# fish-2_0.net
KiCad netlist of a schematic drawn in EAGLE
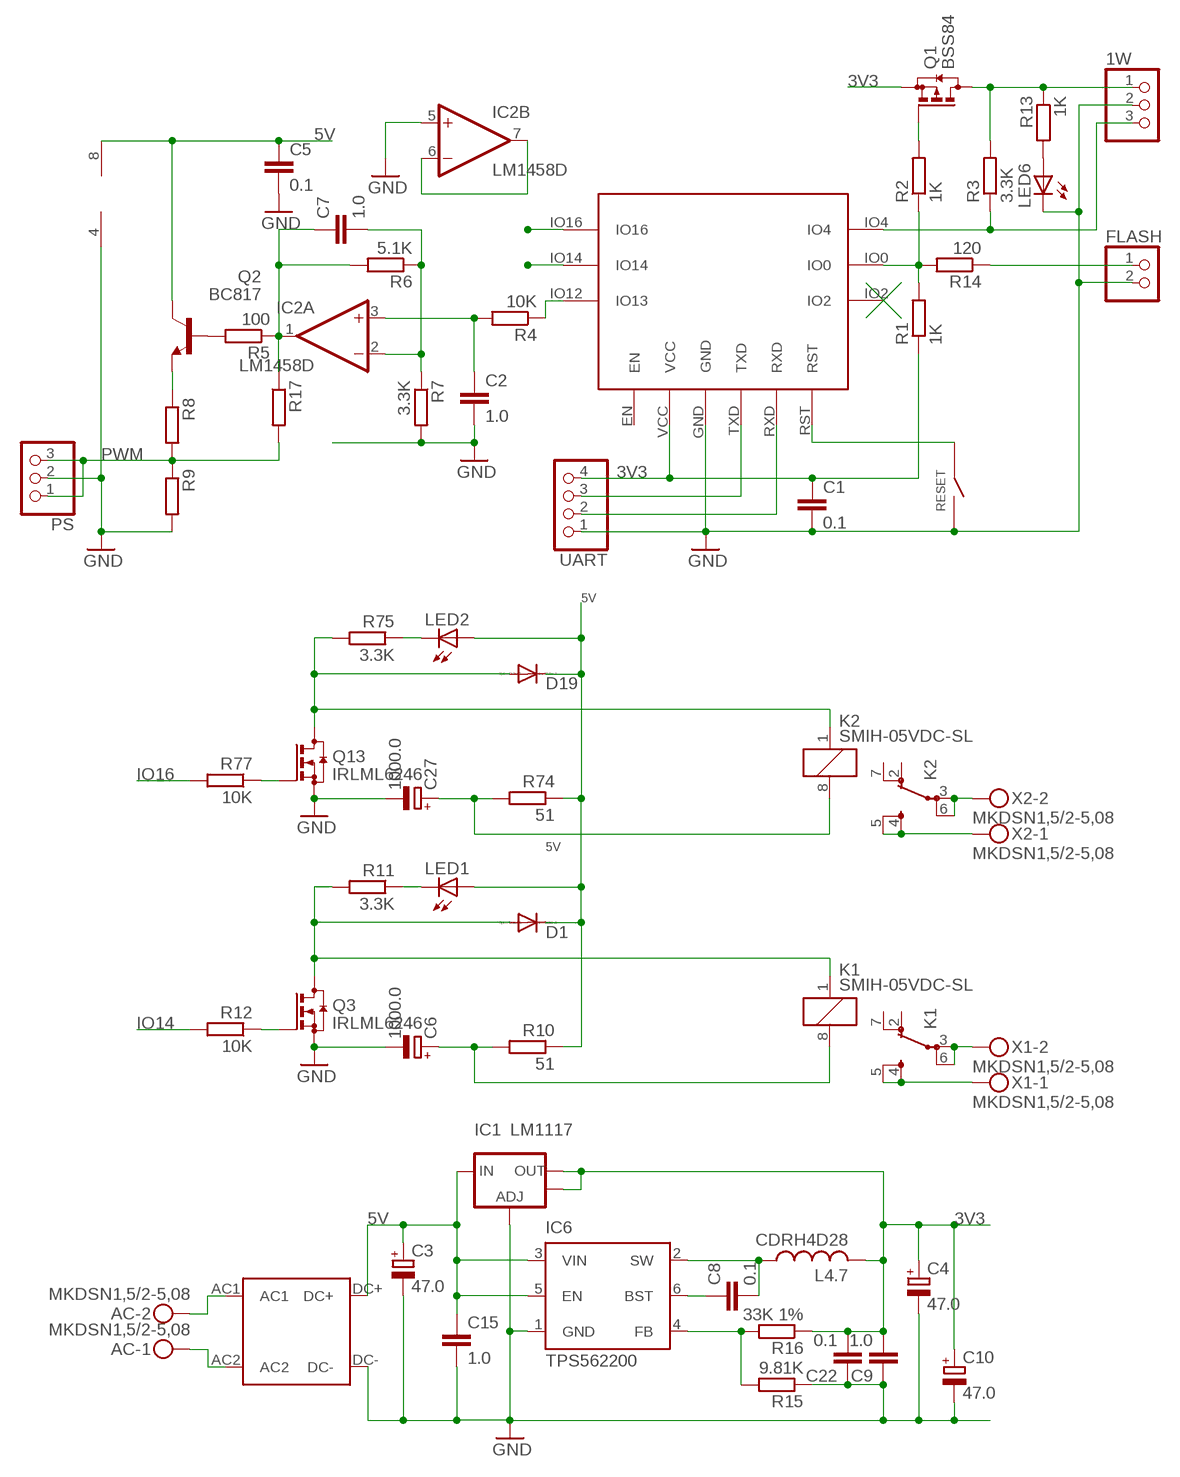
[diagram p0: schematic, sheet 1]

(export (version "E")
  (design (tool "Eeschema 10.0.6"))
  (components
    (comp (ref "1W")
      (value "PINHD-1X3/90")
      (footprint "eagle-import:1X03_90")
      (libsource (lib "eagle-import") (part "PINHD-1X3/90"))
    )
    (comp (ref "AC")
      (value "MKDSN1,5/2-5,08")
      (footprint "eagle-import:MKDSN1,5_2-5,08")
      (libsource (lib "eagle-import") (part "MKDSN1,5/2-5,08"))
    )
    (comp (ref "C1")
      (value "0.1")
      (footprint "eagle-import:C0805")
      (libsource (lib "eagle-import") (part "C-EUC0805"))
    )
    (comp (ref "C2")
      (value "1.0")
      (footprint "eagle-import:C0805")
      (libsource (lib "eagle-import") (part "C-EUC0805"))
    )
    (comp (ref "C3")
      (value "47.0")
      (footprint "eagle-import:SMC_D")
      (libsource (lib "eagle-import") (part "CPOL-EUSMCD"))
    )
    (comp (ref "C4")
      (value "47.0")
      (footprint "eagle-import:SMC_B")
      (libsource (lib "eagle-import") (part "CPOL-EUSMCB"))
    )
    (comp (ref "C5")
      (value "0.1")
      (footprint "eagle-import:C0805")
      (libsource (lib "eagle-import") (part "C-EUC0805"))
    )
    (comp (ref "C6")
      (value "1000.0")
      (footprint "eagle-import:E3,5-8")
      (libsource (lib "eagle-import") (part "CPOL-EUE3.5-8"))
    )
    (comp (ref "C7")
      (value "1.0")
      (footprint "eagle-import:C0805")
      (libsource (lib "eagle-import") (part "C-EUC0805"))
    )
    (comp (ref "C8")
      (value "0.1")
      (footprint "eagle-import:C0805")
      (libsource (lib "eagle-import") (part "C-EUC0805"))
    )
    (comp (ref "C9")
      (value "1.0")
      (footprint "eagle-import:C0805")
      (libsource (lib "eagle-import") (part "C-EUC0805"))
    )
    (comp (ref "C10")
      (value "47.0")
      (footprint "eagle-import:SMC_D")
      (libsource (lib "eagle-import") (part "CPOL-EUSMCD"))
    )
    (comp (ref "C15")
      (value "1.0")
      (footprint "eagle-import:C0805")
      (libsource (lib "eagle-import") (part "C-EUC0805"))
    )
    (comp (ref "C22")
      (value "0.1")
      (footprint "eagle-import:C0805")
      (libsource (lib "eagle-import") (part "C-EUC0805"))
    )
    (comp (ref "C27")
      (value "1000.0")
      (footprint "eagle-import:E3,5-8")
      (libsource (lib "eagle-import") (part "CPOL-EUE3.5-8"))
    )
    (comp (ref "D1")
      (value "DIODE-SOD123")
      (footprint "eagle-import:SOD123")
      (libsource (lib "eagle-import") (part "DIODE-SOD123"))
    )
    (comp (ref "D19")
      (value "DIODE-SOD123")
      (footprint "eagle-import:SOD123")
      (libsource (lib "eagle-import") (part "DIODE-SOD123"))
    )
    (comp (ref "ESP-M3")
      (value "ESP-M3")
      (footprint "eagle-import:ESP-M3")
      (libsource (lib "eagle-import") (part "ESP-M3"))
    )
    (comp (ref "FLASH")
      (value "PINHD-1X2/90")
      (footprint "eagle-import:1X02_90")
      (libsource (lib "eagle-import") (part "PINHD-1X2/90"))
    )
    (comp (ref "IC1")
      (value "LM1117")
      (footprint "eagle-import:SOT223")
      (libsource (lib "eagle-import") (part "V_REG_LM1117SOT223"))
    )
    (comp (ref "IC2")
      (value "LM1458D")
      (footprint "eagle-import:SO08")
      (libsource (lib "eagle-import") (part "1458DLM"))
    )
    (comp (ref "IC6")
      (value "TPS562200")
      (footprint "eagle-import:TSOT23-6_DDC")
      (libsource (lib "eagle-import") (part "TPS56X200"))
    )
    (comp (ref "K1")
      (value "SMIH-05VDC-SL")
      (footprint "eagle-import:FTR-K1C")
      (libsource (lib "eagle-import") (part "FTR-K1C"))
    )
    (comp (ref "K2")
      (value "SMIH-05VDC-SL")
      (footprint "eagle-import:FTR-K1C")
      (libsource (lib "eagle-import") (part "FTR-K1C"))
    )
    (comp (ref "L4.7")
      (value "CDRH4D28")
      (footprint "eagle-import:CDRH4D28")
      (libsource (lib "eagle-import") (part "CDRH4D28"))
    )
    (comp (ref "LED1")
      (value "LEDSMT1206")
      (footprint "eagle-import:1206")
      (libsource (lib "eagle-import") (part "LEDSMT1206"))
    )
    (comp (ref "LED2")
      (value "LEDSMT1206")
      (footprint "eagle-import:1206")
      (libsource (lib "eagle-import") (part "LEDSMT1206"))
    )
    (comp (ref "LED6")
      (value "LEDSMT1206")
      (footprint "eagle-import:1206")
      (libsource (lib "eagle-import") (part "LEDSMT1206"))
    )
    (comp (ref "PS")
      (value "PINHD-1X3/90")
      (footprint "eagle-import:1X03_90")
      (libsource (lib "eagle-import") (part "PINHD-1X3/90"))
    )
    (comp (ref "Q1")
      (value "BSS84")
      (footprint "eagle-import:SOT23")
      (libsource (lib "eagle-import") (part "BSS84"))
    )
    (comp (ref "Q2")
      (value "BC817")
      (footprint "eagle-import:SOT23-BEC")
      (libsource (lib "eagle-import") (part "BC817SMD-40"))
    )
    (comp (ref "Q3")
      (value "IRLML6246")
      (footprint "eagle-import:SOT23")
      (libsource (lib "eagle-import") (part "BSS123"))
    )
    (comp (ref "Q13")
      (value "IRLML6246")
      (footprint "eagle-import:SOT23")
      (libsource (lib "eagle-import") (part "BSS123"))
    )
    (comp (ref "R1")
      (value "1K")
      (footprint "eagle-import:R0603")
      (libsource (lib "eagle-import") (part "R-EU_R0603"))
    )
    (comp (ref "R2")
      (value "1K")
      (footprint "eagle-import:R0603")
      (libsource (lib "eagle-import") (part "R-EU_R0603"))
    )
    (comp (ref "R3")
      (value "3.3K")
      (footprint "eagle-import:R0603")
      (libsource (lib "eagle-import") (part "R-EU_R0603"))
    )
    (comp (ref "R4")
      (value "10K")
      (footprint "eagle-import:R0603")
      (libsource (lib "eagle-import") (part "R-EU_R0603"))
    )
    (comp (ref "R5")
      (value "100")
      (footprint "eagle-import:R0603")
      (libsource (lib "eagle-import") (part "R-EU_R0603"))
    )
    (comp (ref "R6")
      (value "5.1K")
      (footprint "eagle-import:R0603")
      (libsource (lib "eagle-import") (part "R-EU_R0603"))
    )
    (comp (ref "R7")
      (value "3.3K")
      (footprint "eagle-import:R0603")
      (libsource (lib "eagle-import") (part "R-EU_R0603"))
    )
    (comp (ref "R8")
      (value "R-EU_R0603")
      (footprint "eagle-import:R0603")
      (libsource (lib "eagle-import") (part "R-EU_R0603"))
    )
    (comp (ref "R9")
      (value "R-EU_R0603")
      (footprint "eagle-import:R0603")
      (libsource (lib "eagle-import") (part "R-EU_R0603"))
    )
    (comp (ref "R10")
      (value "51")
      (footprint "eagle-import:R1206")
      (libsource (lib "eagle-import") (part "R-EU_R1206"))
    )
    (comp (ref "R11")
      (value "3.3K")
      (footprint "eagle-import:R0603")
      (libsource (lib "eagle-import") (part "R-EU_R0603"))
    )
    (comp (ref "R12")
      (value "10K")
      (footprint "eagle-import:R0603")
      (libsource (lib "eagle-import") (part "R-EU_R0603"))
    )
    (comp (ref "R13")
      (value "1K")
      (footprint "eagle-import:R0603")
      (libsource (lib "eagle-import") (part "R-EU_R0603"))
    )
    (comp (ref "R14")
      (value "120")
      (footprint "eagle-import:R0603")
      (libsource (lib "eagle-import") (part "R-EU_R0603"))
    )
    (comp (ref "R15")
      (value "9.81K")
      (footprint "eagle-import:R0603")
      (libsource (lib "eagle-import") (part "R-EU_R0603"))
    )
    (comp (ref "R16")
      (value "33K 1%")
      (footprint "eagle-import:R0603")
      (libsource (lib "eagle-import") (part "R-EU_R0603"))
    )
    (comp (ref "R17")
      (value "R-EU_R0603")
      (footprint "eagle-import:R0603")
      (libsource (lib "eagle-import") (part "R-EU_R0603"))
    )
    (comp (ref "R74")
      (value "51")
      (footprint "eagle-import:R1206")
      (libsource (lib "eagle-import") (part "R-EU_R1206"))
    )
    (comp (ref "R75")
      (value "3.3K")
      (footprint "eagle-import:R0603")
      (libsource (lib "eagle-import") (part "R-EU_R0603"))
    )
    (comp (ref "R77")
      (value "10K")
      (footprint "eagle-import:R0603")
      (libsource (lib "eagle-import") (part "R-EU_R0603"))
    )
    (comp (ref "RESET")
      (value "TACT3X4")
      (footprint "eagle-import:TACT3X4")
      (libsource (lib "eagle-import") (part "TACT3X4"))
    )
    (comp (ref "U$1")
      (value "AC-DC/10W-12V")
      (footprint "eagle-import:AC-DC_10W")
      (libsource (lib "eagle-import") (part "AC-DC/10W-12V"))
    )
    (comp (ref "UART")
      (value "PINHD-1X4/90")
      (footprint "eagle-import:1X04_90")
      (libsource (lib "eagle-import") (part "PINHD-1X4/90"))
    )
    (comp (ref "X1")
      (value "MKDSN1,5/2-5,08")
      (footprint "eagle-import:MKDSN1,5_2-5,08")
      (libsource (lib "eagle-import") (part "MKDSN1,5/2-5,08"))
    )
    (comp (ref "X2")
      (value "MKDSN1,5/2-5,08")
      (footprint "eagle-import:MKDSN1,5_2-5,08")
      (libsource (lib "eagle-import") (part "MKDSN1,5/2-5,08"))
    )
  )
  (nets
    (net (code "1") (name "/3V3") (class "Default")
      (node (ref "C1") (pin "1") (pinfunction "1_1") (pintype "passive"))
      (node (ref "C10") (pin "+") (pinfunction "+_+") (pintype "passive"))
      (node (ref "C22") (pin "2") (pinfunction "2_2") (pintype "passive"))
      (node (ref "C4") (pin "+") (pinfunction "+_+") (pintype "passive"))
      (node (ref "C9") (pin "2") (pinfunction "2_2") (pintype "passive"))
      (node (ref "ESP-M3") (pin "VCC") (pinfunction "VCC_VCC") (pintype "bidirectional"))
      (node (ref "IC1") (pin "2") (pinfunction "OUT_2") (pintype "output"))
      (node (ref "IC1") (pin "4") (pinfunction "OUT_4") (pintype "output"))
      (node (ref "L4.7") (pin "P$2") (pinfunction "2_P$2") (pintype "passive"))
      (node (ref "Q1") (pin "2") (pinfunction "S_2") (pintype "passive"))
      (node (ref "R1") (pin "1") (pinfunction "1_1") (pintype "passive"))
      (node (ref "R16") (pin "1") (pinfunction "1_1") (pintype "passive"))
      (node (ref "UART") (pin "4") (pinfunction "4_4") (pintype "passive"))
    )
    (net (code "2") (name "/5V") (class "Default")
      (node (ref "C15") (pin "1") (pinfunction "1_1") (pintype "passive"))
      (node (ref "C3") (pin "+") (pinfunction "+_+") (pintype "passive"))
      (node (ref "C5") (pin "1") (pinfunction "1_1") (pintype "passive"))
      (node (ref "D1") (pin "C") (pinfunction "C_C") (pintype "passive"))
      (node (ref "D19") (pin "C") (pinfunction "C_C") (pintype "passive"))
      (node (ref "IC1") (pin "3") (pinfunction "IN_3") (pintype "input"))
      (node (ref "IC2") (pin "8") (pinfunction "V+_8") (pintype "power_in"))
      (node (ref "IC6") (pin "3") (pinfunction "VIN_3") (pintype "input"))
      (node (ref "IC6") (pin "5") (pinfunction "EN_5") (pintype "input"))
      (node (ref "LED1") (pin "A") (pinfunction "A_A") (pintype "passive"))
      (node (ref "LED2") (pin "A") (pinfunction "A_A") (pintype "passive"))
      (node (ref "Q2") (pin "C") (pinfunction "C_C") (pintype "passive"))
      (node (ref "R10") (pin "1") (pinfunction "1_1") (pintype "passive"))
      (node (ref "R74") (pin "1") (pinfunction "1_1") (pintype "passive"))
      (node (ref "U$1") (pin "DC+") (pinfunction "DC+_DC+") (pintype "power_in"))
    )
    (net (code "3") (name "/IO14") (class "Default")
      (node (ref "ESP-M3") (pin "IO14") (pinfunction "IO14_IO14") (pintype "bidirectional"))
      (node (ref "R12") (pin "2") (pinfunction "2_2") (pintype "passive"))
    )
    (net (code "4") (name "/IO16") (class "Default")
      (node (ref "ESP-M3") (pin "IO16") (pinfunction "IO16_IO16") (pintype "bidirectional"))
      (node (ref "R77") (pin "2") (pinfunction "2_2") (pintype "passive"))
    )
    (net (code "5") (name "/PWM") (class "Default")
      (node (ref "PS") (pin "1") (pinfunction "1_1") (pintype "passive"))
      (node (ref "PS") (pin "3") (pinfunction "3_3") (pintype "passive"))
      (node (ref "R17") (pin "2") (pinfunction "2_2") (pintype "passive"))
      (node (ref "R8") (pin "2") (pinfunction "2_2") (pintype "passive"))
      (node (ref "R9") (pin "1") (pinfunction "1_1") (pintype "passive"))
    )
    (net (code "6") (name "GND") (class "Default")
      (node (ref "1W") (pin "2") (pinfunction "2_2") (pintype "passive"))
      (node (ref "C1") (pin "2") (pinfunction "2_2") (pintype "passive"))
      (node (ref "C10") (pin "-") (pinfunction "-_-") (pintype "passive"))
      (node (ref "C15") (pin "2") (pinfunction "2_2") (pintype "passive"))
      (node (ref "C2") (pin "2") (pinfunction "2_2") (pintype "passive"))
      (node (ref "C22") (pin "1") (pinfunction "1_1") (pintype "passive"))
      (node (ref "C27") (pin "-") (pinfunction "-_-") (pintype "passive"))
      (node (ref "C3") (pin "-") (pinfunction "-_-") (pintype "passive"))
      (node (ref "C4") (pin "-") (pinfunction "-_-") (pintype "passive"))
      (node (ref "C5") (pin "2") (pinfunction "2_2") (pintype "passive"))
      (node (ref "C6") (pin "-") (pinfunction "-_-") (pintype "passive"))
      (node (ref "C9") (pin "1") (pinfunction "1_1") (pintype "passive"))
      (node (ref "ESP-M3") (pin "GND") (pinfunction "GND_GND") (pintype "bidirectional"))
      (node (ref "FLASH") (pin "2") (pinfunction "2_2") (pintype "passive"))
      (node (ref "IC1") (pin "1") (pinfunction "ADJ_1") (pintype "input"))
      (node (ref "IC2") (pin "4") (pinfunction "V-_4") (pintype "power_in"))
      (node (ref "IC2") (pin "5") (pinfunction "+IN_5") (pintype "input"))
      (node (ref "IC6") (pin "1") (pinfunction "GND_1") (pintype "power_in"))
      (node (ref "LED6") (pin "C") (pinfunction "C_C") (pintype "passive"))
      (node (ref "PS") (pin "2") (pinfunction "2_2") (pintype "passive"))
      (node (ref "Q13") (pin "2") (pinfunction "S_2") (pintype "passive"))
      (node (ref "Q3") (pin "2") (pinfunction "S_2") (pintype "passive"))
      (node (ref "R15") (pin "1") (pinfunction "1_1") (pintype "passive"))
      (node (ref "R7") (pin "2") (pinfunction "2_2") (pintype "passive"))
      (node (ref "R9") (pin "2") (pinfunction "2_2") (pintype "passive"))
      (node (ref "RESET") (pin "P$2") (pinfunction "P$2_P$2") (pintype "bidirectional"))
      (node (ref "U$1") (pin "DC-") (pinfunction "DC-_DC-") (pintype "power_in"))
      (node (ref "UART") (pin "1") (pinfunction "1_1") (pintype "passive"))
    )
    (net (code "7") (name "Net-(1W-Pad3)") (class "Default")
      (node (ref "1W") (pin "3") (pinfunction "3_3") (pintype "passive"))
      (node (ref "ESP-M3") (pin "IO4") (pinfunction "IO4_IO4") (pintype "bidirectional"))
      (node (ref "R3") (pin "1") (pinfunction "1_1") (pintype "passive"))
    )
    (net (code "8") (name "Net-(ACA-KL)") (class "Default")
      (node (ref "AC") (pin "1") (pinfunction "KL_1") (pintype "passive"))
      (node (ref "U$1") (pin "AC2") (pinfunction "AC2_AC2") (pintype "power_in"))
    )
    (net (code "9") (name "Net-(ACB-KL)") (class "Default")
      (node (ref "AC") (pin "2") (pinfunction "KL_2") (pintype "passive"))
      (node (ref "U$1") (pin "AC1") (pinfunction "AC1_AC1") (pintype "power_in"))
    )
    (net (code "10") (name "Net-(ESP-M3-IO13)") (class "Default")
      (node (ref "ESP-M3") (pin "IO12") (pinfunction "IO13_IO12") (pintype "bidirectional"))
      (node (ref "R4") (pin "1") (pinfunction "1_1") (pintype "passive"))
    )
    (net (code "11") (name "Net-(ESP-M3-PadIO0)") (class "Default")
      (node (ref "ESP-M3") (pin "IO0") (pinfunction "IO0_IO0") (pintype "bidirectional"))
      (node (ref "R1") (pin "2") (pinfunction "2_2") (pintype "passive"))
      (node (ref "R14") (pin "2") (pinfunction "2_2") (pintype "passive"))
      (node (ref "R2") (pin "1") (pinfunction "1_1") (pintype "passive"))
    )
    (net (code "12") (name "Net-(ESP-M3-PadRST)") (class "Default")
      (node (ref "ESP-M3") (pin "RST") (pinfunction "RST_RST") (pintype "bidirectional"))
      (node (ref "RESET") (pin "P$1") (pinfunction "P$1_P$1") (pintype "bidirectional"))
    )
    (net (code "13") (name "Net-(ESP-M3-PadRXD)") (class "Default")
      (node (ref "ESP-M3") (pin "RXD") (pinfunction "RXD_RXD") (pintype "bidirectional"))
      (node (ref "UART") (pin "2") (pinfunction "2_2") (pintype "passive"))
    )
    (net (code "14") (name "Net-(ESP-M3-PadTXD)") (class "Default")
      (node (ref "ESP-M3") (pin "TXD") (pinfunction "TXD_TXD") (pintype "bidirectional"))
      (node (ref "UART") (pin "3") (pinfunction "3_3") (pintype "passive"))
    )
    (net (code "15") (name "Net-(FLASH-Pad1)") (class "Default")
      (node (ref "FLASH") (pin "1") (pinfunction "1_1") (pintype "passive"))
      (node (ref "R14") (pin "1") (pinfunction "1_1") (pintype "passive"))
    )
    (net (code "16") (name "Net-(IC2A-+IN)") (class "Default")
      (node (ref "C2") (pin "1") (pinfunction "1_1") (pintype "passive"))
      (node (ref "IC2") (pin "3") (pinfunction "+IN_3") (pintype "input"))
      (node (ref "R4") (pin "2") (pinfunction "2_2") (pintype "passive"))
    )
    (net (code "17") (name "Net-(IC2A--IN)") (class "Default")
      (node (ref "C7") (pin "2") (pinfunction "2_2") (pintype "passive"))
      (node (ref "IC2") (pin "2") (pinfunction "-IN_2") (pintype "input"))
      (node (ref "R6") (pin "1") (pinfunction "1_1") (pintype "passive"))
      (node (ref "R7") (pin "1") (pinfunction "1_1") (pintype "passive"))
    )
    (net (code "18") (name "Net-(IC2A-OUT)") (class "Default")
      (node (ref "C7") (pin "1") (pinfunction "1_1") (pintype "passive"))
      (node (ref "IC2") (pin "1") (pinfunction "OUT_1") (pintype "output"))
      (node (ref "R17") (pin "1") (pinfunction "1_1") (pintype "passive"))
      (node (ref "R5") (pin "1") (pinfunction "1_1") (pintype "passive"))
      (node (ref "R6") (pin "2") (pinfunction "2_2") (pintype "passive"))
    )
    (net (code "19") (name "Net-(IC2B--IN)") (class "Default")
      (node (ref "IC2") (pin "6") (pinfunction "-IN_6") (pintype "input"))
      (node (ref "IC2") (pin "7") (pinfunction "OUT_7") (pintype "output"))
    )
    (net (code "20") (name "Net-(IC6-BST)") (class "Default")
      (node (ref "C8") (pin "1") (pinfunction "1_1") (pintype "passive"))
      (node (ref "IC6") (pin "6") (pinfunction "BST_6") (pintype "input"))
    )
    (net (code "21") (name "Net-(IC6-FB)") (class "Default")
      (node (ref "IC6") (pin "4") (pinfunction "FB_4") (pintype "input"))
      (node (ref "R15") (pin "2") (pinfunction "2_2") (pintype "passive"))
      (node (ref "R16") (pin "2") (pinfunction "2_2") (pintype "passive"))
    )
    (net (code "22") (name "Net-(IC6-SW)") (class "Default")
      (node (ref "C8") (pin "2") (pinfunction "2_2") (pintype "passive"))
      (node (ref "IC6") (pin "2") (pinfunction "SW_2") (pintype "passive"))
      (node (ref "L4.7") (pin "P$1") (pinfunction "1_P$1") (pintype "passive"))
    )
    (net (code "23") (name "Net-(K1A-PA)") (class "Default")
      (node (ref "K1") (pin "3") (pinfunction "PA_3") (pintype "passive"))
      (node (ref "K1") (pin "6") (pinfunction "PB_6") (pintype "passive"))
      (node (ref "X1") (pin "2") (pinfunction "KL_2") (pintype "passive"))
    )
    (net (code "24") (name "Net-(K1A-SA)") (class "Default")
      (node (ref "K1") (pin "4") (pinfunction "SA_4") (pintype "passive"))
      (node (ref "K1") (pin "5") (pinfunction "SB_5") (pintype "passive"))
      (node (ref "X1") (pin "1") (pinfunction "KL_1") (pintype "passive"))
    )
    (net (code "25") (name "Net-(K1B-2)") (class "Default")
      (node (ref "C6") (pin "+") (pinfunction "+_+") (pintype "passive"))
      (node (ref "K1") (pin "8") (pinfunction "2_8") (pintype "passive"))
      (node (ref "R10") (pin "2") (pinfunction "2_2") (pintype "passive"))
    )
    (net (code "26") (name "Net-(K2A-PA)") (class "Default")
      (node (ref "K2") (pin "3") (pinfunction "PA_3") (pintype "passive"))
      (node (ref "K2") (pin "6") (pinfunction "PB_6") (pintype "passive"))
      (node (ref "X2") (pin "2") (pinfunction "KL_2") (pintype "passive"))
    )
    (net (code "27") (name "Net-(K2A-SA)") (class "Default")
      (node (ref "K2") (pin "4") (pinfunction "SA_4") (pintype "passive"))
      (node (ref "K2") (pin "5") (pinfunction "SB_5") (pintype "passive"))
      (node (ref "X2") (pin "1") (pinfunction "KL_1") (pintype "passive"))
    )
    (net (code "28") (name "Net-(K2B-2)") (class "Default")
      (node (ref "C27") (pin "+") (pinfunction "+_+") (pintype "passive"))
      (node (ref "K2") (pin "8") (pinfunction "2_8") (pintype "passive"))
      (node (ref "R74") (pin "2") (pinfunction "2_2") (pintype "passive"))
    )
    (net (code "29") (name "Net-(LED1-PadC)") (class "Default")
      (node (ref "LED1") (pin "C") (pinfunction "C_C") (pintype "passive"))
      (node (ref "R11") (pin "1") (pinfunction "1_1") (pintype "passive"))
    )
    (net (code "30") (name "Net-(LED2-PadC)") (class "Default")
      (node (ref "LED2") (pin "C") (pinfunction "C_C") (pintype "passive"))
      (node (ref "R75") (pin "1") (pinfunction "1_1") (pintype "passive"))
    )
    (net (code "31") (name "Net-(LED6-PadA)") (class "Default")
      (node (ref "LED6") (pin "A") (pinfunction "A_A") (pintype "passive"))
      (node (ref "R13") (pin "2") (pinfunction "2_2") (pintype "passive"))
    )
    (net (code "32") (name "Net-(Q1-D)") (class "Default")
      (node (ref "1W") (pin "1") (pinfunction "1_1") (pintype "passive"))
      (node (ref "Q1") (pin "3") (pinfunction "D_3") (pintype "passive"))
      (node (ref "R13") (pin "1") (pinfunction "1_1") (pintype "passive"))
      (node (ref "R3") (pin "2") (pinfunction "2_2") (pintype "passive"))
    )
    (net (code "33") (name "Net-(Q1-G)") (class "Default")
      (node (ref "Q1") (pin "1") (pinfunction "G_1") (pintype "passive"))
      (node (ref "R2") (pin "2") (pinfunction "2_2") (pintype "passive"))
    )
    (net (code "34") (name "Net-(Q2-PadB)") (class "Default")
      (node (ref "Q2") (pin "B") (pinfunction "B_B") (pintype "passive"))
      (node (ref "R5") (pin "2") (pinfunction "2_2") (pintype "passive"))
    )
    (net (code "35") (name "Net-(Q2-PadE)") (class "Default")
      (node (ref "Q2") (pin "E") (pinfunction "E_E") (pintype "passive"))
      (node (ref "R8") (pin "1") (pinfunction "1_1") (pintype "passive"))
    )
    (net (code "36") (name "Net-(Q3-D)") (class "Default")
      (node (ref "D1") (pin "A") (pinfunction "A_A") (pintype "passive"))
      (node (ref "K1") (pin "1") (pinfunction "1_1") (pintype "passive"))
      (node (ref "Q3") (pin "3") (pinfunction "D_3") (pintype "passive"))
      (node (ref "R11") (pin "2") (pinfunction "2_2") (pintype "passive"))
    )
    (net (code "37") (name "Net-(Q3-G)") (class "Default")
      (node (ref "Q3") (pin "1") (pinfunction "G_1") (pintype "passive"))
      (node (ref "R12") (pin "1") (pinfunction "1_1") (pintype "passive"))
    )
    (net (code "38") (name "Net-(Q13-D)") (class "Default")
      (node (ref "D19") (pin "A") (pinfunction "A_A") (pintype "passive"))
      (node (ref "K2") (pin "1") (pinfunction "1_1") (pintype "passive"))
      (node (ref "Q13") (pin "3") (pinfunction "D_3") (pintype "passive"))
      (node (ref "R75") (pin "2") (pinfunction "2_2") (pintype "passive"))
    )
    (net (code "39") (name "Net-(Q13-G)") (class "Default")
      (node (ref "Q13") (pin "1") (pinfunction "G_1") (pintype "passive"))
      (node (ref "R77") (pin "1") (pinfunction "1_1") (pintype "passive"))
    )
    (net (code "40") (name "unconnected-(ESP-M3-PadEN)") (class "Default")
      (node (ref "ESP-M3") (pin "EN") (pinfunction "EN_EN") (pintype "bidirectional"))
    )
    (net (code "41") (name "unconnected-(ESP-M3-PadIO2)") (class "Default")
      (node (ref "ESP-M3") (pin "IO2") (pinfunction "IO2_IO2") (pintype "bidirectional"))
    )
    (net (code "42") (name "unconnected-(K1A-OA-Pad2)") (class "Default")
      (node (ref "K1") (pin "2") (pinfunction "OA_2") (pintype "passive"))
    )
    (net (code "43") (name "unconnected-(K1A-OB-Pad7)") (class "Default")
      (node (ref "K1") (pin "7") (pinfunction "OB_7") (pintype "passive"))
    )
    (net (code "44") (name "unconnected-(K2A-OA-Pad2)") (class "Default")
      (node (ref "K2") (pin "2") (pinfunction "OA_2") (pintype "passive"))
    )
    (net (code "45") (name "unconnected-(K2A-OB-Pad7)") (class "Default")
      (node (ref "K2") (pin "7") (pinfunction "OB_7") (pintype "passive"))
    )
  )
)
